# interlinkP2A.net
KiCad netlist of a schematic drawn in Altium Designer
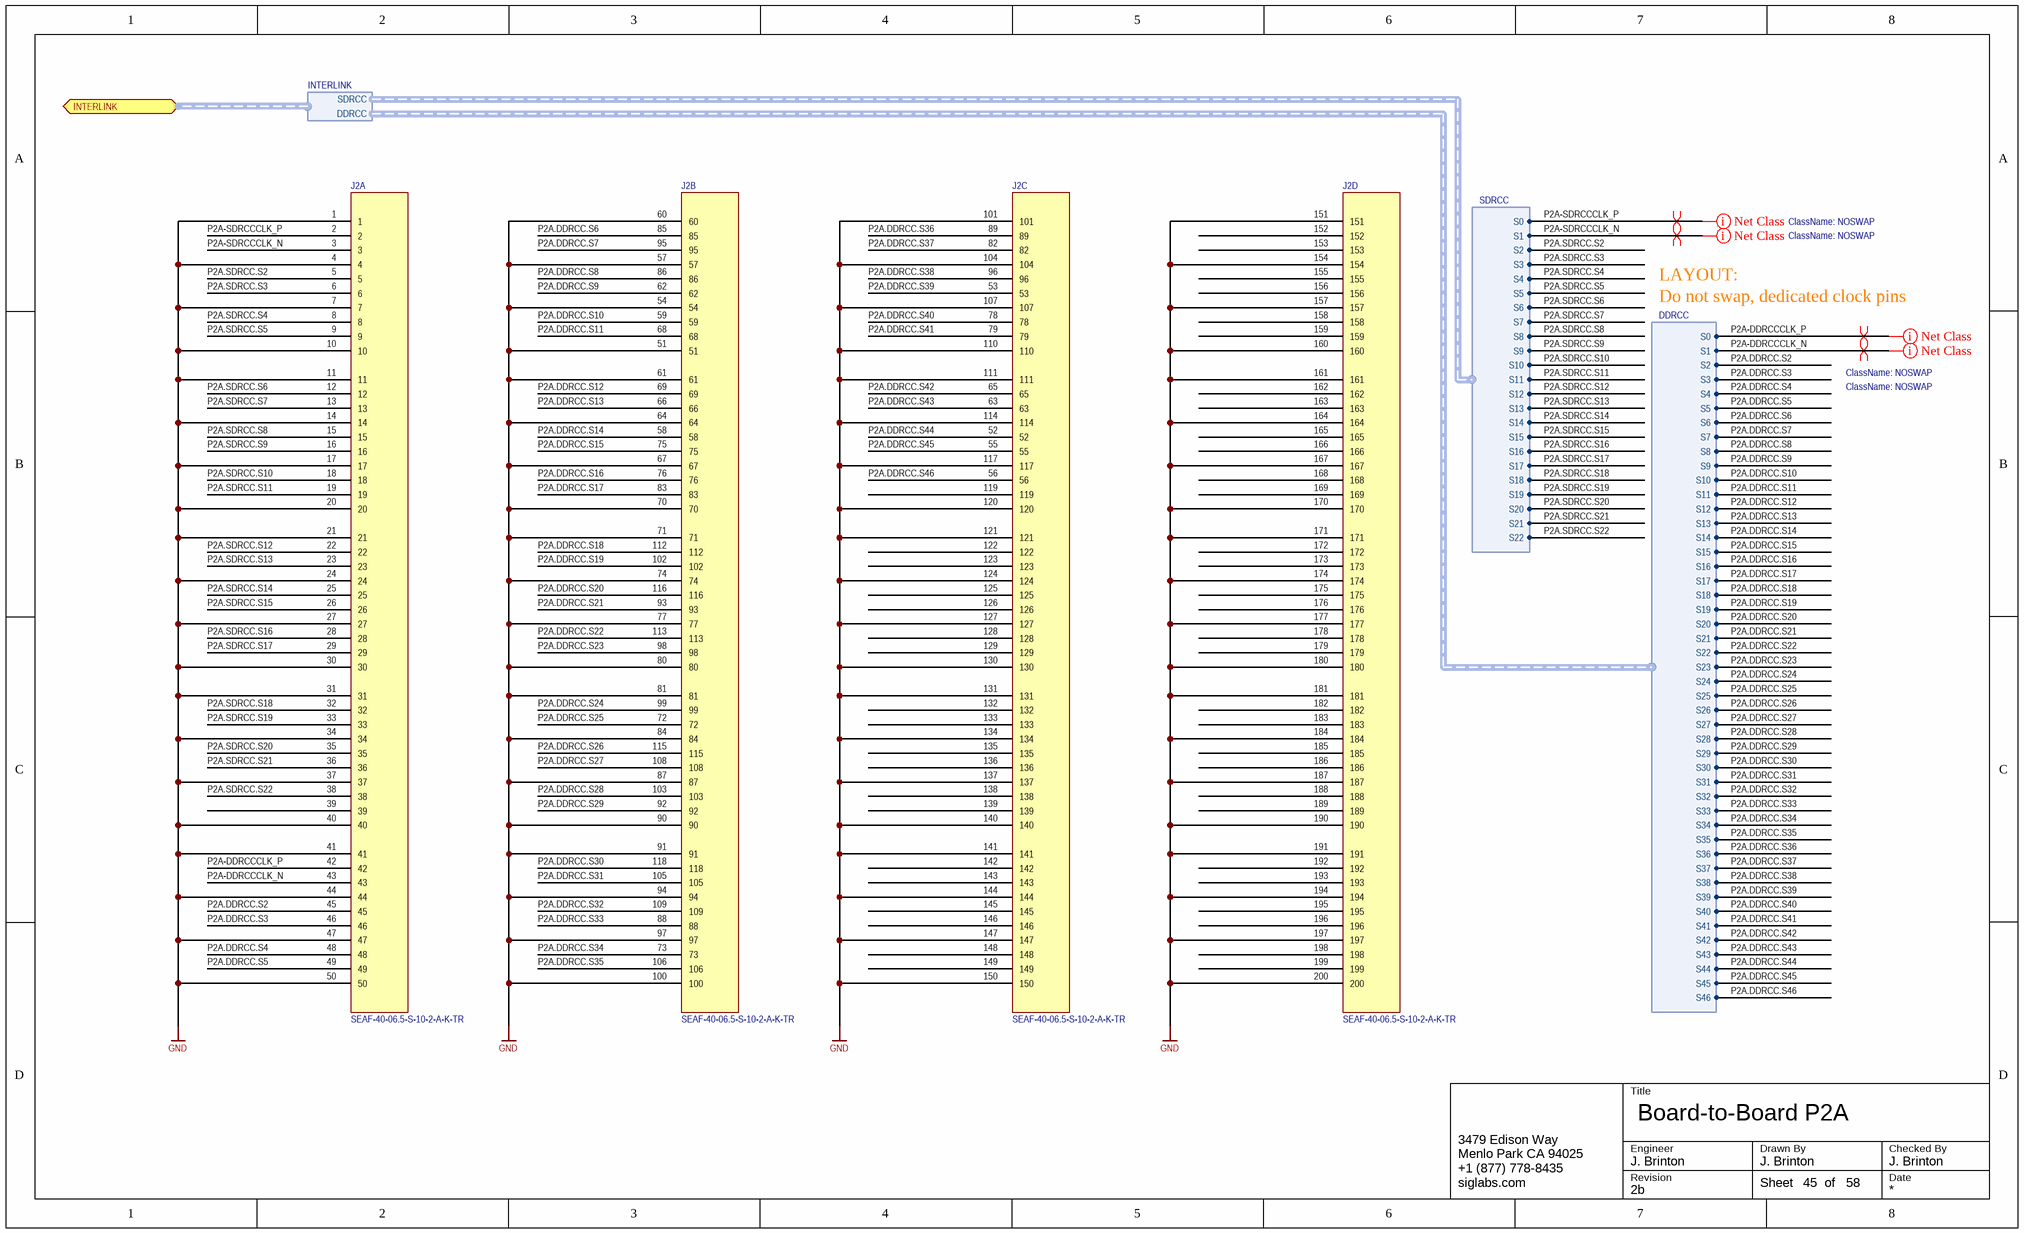
[diagram p0: interlinkP2A.SchDoc]

(export (version "E")
  (design (tool "Eeschema 10.0.6"))
  (components
    (comp (ref "J2")
      (value "SEAF-40-06.5-S-10-2-A-K-TR")
      (footprint "samtec:SEAF-40-06.5-S-10-2-A-K-TR")
      (description "Terminal Array Assembly, Surface Mount, 0.050\" Pitch, 400 Pins")
      (fields (field (name "MANUFACTURER") "Samtec"))
      (libsource (lib "samtec") (part "SEAF-40-06.5-S-10-2-A-K-TR"))
    )
  )
  (nets
    (net (code "5") (name "/P2A-DDRCCCLK_N") (class "Default")
      (node (ref "J2") (pin "43") (pinfunction "43_43") (pintype "passive"))
    )
    (net (code "6") (name "/P2A-DDRCCCLK_P") (class "Default")
      (node (ref "J2") (pin "42") (pinfunction "42_42") (pintype "passive"))
    )
    (net (code "7") (name "/P2A-SDRCCCLK_N") (class "Default")
      (node (ref "J2") (pin "3") (pinfunction "3_3") (pintype "passive"))
    )
    (net (code "8") (name "/P2A-SDRCCCLK_P") (class "Default")
      (node (ref "J2") (pin "2") (pinfunction "2_2") (pintype "passive"))
    )
    (net (code "9") (name "/P2A.DDRCC.S2") (class "Default")
      (node (ref "J2") (pin "45") (pinfunction "45_45") (pintype "passive"))
    )
    (net (code "10") (name "/P2A.DDRCC.S3") (class "Default")
      (node (ref "J2") (pin "46") (pinfunction "46_46") (pintype "passive"))
    )
    (net (code "11") (name "/P2A.DDRCC.S4") (class "Default")
      (node (ref "J2") (pin "48") (pinfunction "48_48") (pintype "passive"))
    )
    (net (code "12") (name "/P2A.DDRCC.S5") (class "Default")
      (node (ref "J2") (pin "49") (pinfunction "49_49") (pintype "passive"))
    )
    (net (code "13") (name "/P2A.DDRCC.S6") (class "Default")
      (node (ref "J2") (pin "85") (pinfunction "85_85") (pintype "passive"))
    )
    (net (code "14") (name "/P2A.DDRCC.S7") (class "Default")
      (node (ref "J2") (pin "95") (pinfunction "95_95") (pintype "passive"))
    )
    (net (code "15") (name "/P2A.DDRCC.S8") (class "Default")
      (node (ref "J2") (pin "86") (pinfunction "86_86") (pintype "passive"))
    )
    (net (code "16") (name "/P2A.DDRCC.S9") (class "Default")
      (node (ref "J2") (pin "62") (pinfunction "62_62") (pintype "passive"))
    )
    (net (code "17") (name "/P2A.DDRCC.S10") (class "Default")
      (node (ref "J2") (pin "59") (pinfunction "59_59") (pintype "passive"))
    )
    (net (code "18") (name "/P2A.DDRCC.S11") (class "Default")
      (node (ref "J2") (pin "68") (pinfunction "68_68") (pintype "passive"))
    )
    (net (code "19") (name "/P2A.DDRCC.S12") (class "Default")
      (node (ref "J2") (pin "69") (pinfunction "69_69") (pintype "passive"))
    )
    (net (code "20") (name "/P2A.DDRCC.S13") (class "Default")
      (node (ref "J2") (pin "66") (pinfunction "66_66") (pintype "passive"))
    )
    (net (code "21") (name "/P2A.DDRCC.S14") (class "Default")
      (node (ref "J2") (pin "58") (pinfunction "58_58") (pintype "passive"))
    )
    (net (code "22") (name "/P2A.DDRCC.S15") (class "Default")
      (node (ref "J2") (pin "75") (pinfunction "75_75") (pintype "passive"))
    )
    (net (code "23") (name "/P2A.DDRCC.S16") (class "Default")
      (node (ref "J2") (pin "76") (pinfunction "76_76") (pintype "passive"))
    )
    (net (code "24") (name "/P2A.DDRCC.S17") (class "Default")
      (node (ref "J2") (pin "83") (pinfunction "83_83") (pintype "passive"))
    )
    (net (code "25") (name "/P2A.DDRCC.S18") (class "Default")
      (node (ref "J2") (pin "112") (pinfunction "112_112") (pintype "passive"))
    )
    (net (code "26") (name "/P2A.DDRCC.S19") (class "Default")
      (node (ref "J2") (pin "102") (pinfunction "102_102") (pintype "passive"))
    )
    (net (code "27") (name "/P2A.DDRCC.S20") (class "Default")
      (node (ref "J2") (pin "116") (pinfunction "116_116") (pintype "passive"))
    )
    (net (code "28") (name "/P2A.DDRCC.S21") (class "Default")
      (node (ref "J2") (pin "93") (pinfunction "93_93") (pintype "passive"))
    )
    (net (code "29") (name "/P2A.DDRCC.S22") (class "Default")
      (node (ref "J2") (pin "113") (pinfunction "113_113") (pintype "passive"))
    )
    (net (code "30") (name "/P2A.DDRCC.S23") (class "Default")
      (node (ref "J2") (pin "98") (pinfunction "98_98") (pintype "passive"))
    )
    (net (code "31") (name "/P2A.DDRCC.S24") (class "Default")
      (node (ref "J2") (pin "99") (pinfunction "99_99") (pintype "passive"))
    )
    (net (code "32") (name "/P2A.DDRCC.S25") (class "Default")
      (node (ref "J2") (pin "72") (pinfunction "72_72") (pintype "passive"))
    )
    (net (code "33") (name "/P2A.DDRCC.S26") (class "Default")
      (node (ref "J2") (pin "115") (pinfunction "115_115") (pintype "passive"))
    )
    (net (code "34") (name "/P2A.DDRCC.S27") (class "Default")
      (node (ref "J2") (pin "108") (pinfunction "108_108") (pintype "passive"))
    )
    (net (code "35") (name "/P2A.DDRCC.S28") (class "Default")
      (node (ref "J2") (pin "103") (pinfunction "103_103") (pintype "passive"))
    )
    (net (code "36") (name "/P2A.DDRCC.S29") (class "Default")
      (node (ref "J2") (pin "92") (pinfunction "92_92") (pintype "passive"))
    )
    (net (code "37") (name "/P2A.DDRCC.S30") (class "Default")
      (node (ref "J2") (pin "118") (pinfunction "118_118") (pintype "passive"))
    )
    (net (code "38") (name "/P2A.DDRCC.S31") (class "Default")
      (node (ref "J2") (pin "105") (pinfunction "105_105") (pintype "passive"))
    )
    (net (code "39") (name "/P2A.DDRCC.S32") (class "Default")
      (node (ref "J2") (pin "109") (pinfunction "109_109") (pintype "passive"))
    )
    (net (code "40") (name "/P2A.DDRCC.S33") (class "Default")
      (node (ref "J2") (pin "88") (pinfunction "88_88") (pintype "passive"))
    )
    (net (code "41") (name "/P2A.DDRCC.S34") (class "Default")
      (node (ref "J2") (pin "73") (pinfunction "73_73") (pintype "passive"))
    )
    (net (code "42") (name "/P2A.DDRCC.S35") (class "Default")
      (node (ref "J2") (pin "106") (pinfunction "106_106") (pintype "passive"))
    )
    (net (code "43") (name "/P2A.DDRCC.S36") (class "Default")
      (node (ref "J2") (pin "89") (pinfunction "89_89") (pintype "passive"))
    )
    (net (code "44") (name "/P2A.DDRCC.S37") (class "Default")
      (node (ref "J2") (pin "82") (pinfunction "82_82") (pintype "passive"))
    )
    (net (code "45") (name "/P2A.DDRCC.S38") (class "Default")
      (node (ref "J2") (pin "96") (pinfunction "96_96") (pintype "passive"))
    )
    (net (code "46") (name "/P2A.DDRCC.S39") (class "Default")
      (node (ref "J2") (pin "53") (pinfunction "53_53") (pintype "passive"))
    )
    (net (code "47") (name "/P2A.DDRCC.S40") (class "Default")
      (node (ref "J2") (pin "78") (pinfunction "78_78") (pintype "passive"))
    )
    (net (code "48") (name "/P2A.DDRCC.S41") (class "Default")
      (node (ref "J2") (pin "79") (pinfunction "79_79") (pintype "passive"))
    )
    (net (code "49") (name "/P2A.DDRCC.S42") (class "Default")
      (node (ref "J2") (pin "65") (pinfunction "65_65") (pintype "passive"))
    )
    (net (code "50") (name "/P2A.DDRCC.S43") (class "Default")
      (node (ref "J2") (pin "63") (pinfunction "63_63") (pintype "passive"))
    )
    (net (code "51") (name "/P2A.DDRCC.S44") (class "Default")
      (node (ref "J2") (pin "52") (pinfunction "52_52") (pintype "passive"))
    )
    (net (code "52") (name "/P2A.DDRCC.S45") (class "Default")
      (node (ref "J2") (pin "55") (pinfunction "55_55") (pintype "passive"))
    )
    (net (code "53") (name "/P2A.DDRCC.S46") (class "Default")
      (node (ref "J2") (pin "56") (pinfunction "56_56") (pintype "passive"))
    )
    (net (code "54") (name "/P2A.SDRCC.S2") (class "Default")
      (node (ref "J2") (pin "5") (pinfunction "5_5") (pintype "passive"))
    )
    (net (code "55") (name "/P2A.SDRCC.S3") (class "Default")
      (node (ref "J2") (pin "6") (pinfunction "6_6") (pintype "passive"))
    )
    (net (code "56") (name "/P2A.SDRCC.S4") (class "Default")
      (node (ref "J2") (pin "8") (pinfunction "8_8") (pintype "passive"))
    )
    (net (code "57") (name "/P2A.SDRCC.S5") (class "Default")
      (node (ref "J2") (pin "9") (pinfunction "9_9") (pintype "passive"))
    )
    (net (code "58") (name "/P2A.SDRCC.S6") (class "Default")
      (node (ref "J2") (pin "12") (pinfunction "12_12") (pintype "passive"))
    )
    (net (code "59") (name "/P2A.SDRCC.S7") (class "Default")
      (node (ref "J2") (pin "13") (pinfunction "13_13") (pintype "passive"))
    )
    (net (code "60") (name "/P2A.SDRCC.S8") (class "Default")
      (node (ref "J2") (pin "15") (pinfunction "15_15") (pintype "passive"))
    )
    (net (code "61") (name "/P2A.SDRCC.S9") (class "Default")
      (node (ref "J2") (pin "16") (pinfunction "16_16") (pintype "passive"))
    )
    (net (code "62") (name "/P2A.SDRCC.S10") (class "Default")
      (node (ref "J2") (pin "18") (pinfunction "18_18") (pintype "passive"))
    )
    (net (code "63") (name "/P2A.SDRCC.S11") (class "Default")
      (node (ref "J2") (pin "19") (pinfunction "19_19") (pintype "passive"))
    )
    (net (code "64") (name "/P2A.SDRCC.S12") (class "Default")
      (node (ref "J2") (pin "22") (pinfunction "22_22") (pintype "passive"))
    )
    (net (code "65") (name "/P2A.SDRCC.S13") (class "Default")
      (node (ref "J2") (pin "23") (pinfunction "23_23") (pintype "passive"))
    )
    (net (code "66") (name "/P2A.SDRCC.S14") (class "Default")
      (node (ref "J2") (pin "25") (pinfunction "25_25") (pintype "passive"))
    )
    (net (code "67") (name "/P2A.SDRCC.S15") (class "Default")
      (node (ref "J2") (pin "26") (pinfunction "26_26") (pintype "passive"))
    )
    (net (code "68") (name "/P2A.SDRCC.S16") (class "Default")
      (node (ref "J2") (pin "28") (pinfunction "28_28") (pintype "passive"))
    )
    (net (code "69") (name "/P2A.SDRCC.S17") (class "Default")
      (node (ref "J2") (pin "29") (pinfunction "29_29") (pintype "passive"))
    )
    (net (code "70") (name "/P2A.SDRCC.S18") (class "Default")
      (node (ref "J2") (pin "32") (pinfunction "32_32") (pintype "passive"))
    )
    (net (code "71") (name "/P2A.SDRCC.S19") (class "Default")
      (node (ref "J2") (pin "33") (pinfunction "33_33") (pintype "passive"))
    )
    (net (code "72") (name "/P2A.SDRCC.S20") (class "Default")
      (node (ref "J2") (pin "35") (pinfunction "35_35") (pintype "passive"))
    )
    (net (code "73") (name "/P2A.SDRCC.S21") (class "Default")
      (node (ref "J2") (pin "36") (pinfunction "36_36") (pintype "passive"))
    )
    (net (code "74") (name "/P2A.SDRCC.S22") (class "Default")
      (node (ref "J2") (pin "38") (pinfunction "38_38") (pintype "passive"))
    )
    (net (code "77") (name "GND") (class "Default")
      (node (ref "J2") (pin "1") (pinfunction "1_1") (pintype "passive"))
      (node (ref "J2") (pin "10") (pinfunction "10_10") (pintype "passive"))
      (node (ref "J2") (pin "100") (pinfunction "100_100") (pintype "passive"))
      (node (ref "J2") (pin "101") (pinfunction "101_101") (pintype "passive"))
      (node (ref "J2") (pin "104") (pinfunction "104_104") (pintype "passive"))
      (node (ref "J2") (pin "107") (pinfunction "107_107") (pintype "passive"))
      (node (ref "J2") (pin "11") (pinfunction "11_11") (pintype "passive"))
      (node (ref "J2") (pin "110") (pinfunction "110_110") (pintype "passive"))
      (node (ref "J2") (pin "111") (pinfunction "111_111") (pintype "passive"))
      (node (ref "J2") (pin "114") (pinfunction "114_114") (pintype "passive"))
      (node (ref "J2") (pin "117") (pinfunction "117_117") (pintype "passive"))
      (node (ref "J2") (pin "120") (pinfunction "120_120") (pintype "passive"))
      (node (ref "J2") (pin "121") (pinfunction "121_121") (pintype "passive"))
      (node (ref "J2") (pin "124") (pinfunction "124_124") (pintype "passive"))
      (node (ref "J2") (pin "127") (pinfunction "127_127") (pintype "passive"))
      (node (ref "J2") (pin "130") (pinfunction "130_130") (pintype "passive"))
      (node (ref "J2") (pin "131") (pinfunction "131_131") (pintype "passive"))
      (node (ref "J2") (pin "134") (pinfunction "134_134") (pintype "passive"))
      (node (ref "J2") (pin "137") (pinfunction "137_137") (pintype "passive"))
      (node (ref "J2") (pin "14") (pinfunction "14_14") (pintype "passive"))
      (node (ref "J2") (pin "140") (pinfunction "140_140") (pintype "passive"))
      (node (ref "J2") (pin "141") (pinfunction "141_141") (pintype "passive"))
      (node (ref "J2") (pin "144") (pinfunction "144_144") (pintype "passive"))
      (node (ref "J2") (pin "147") (pinfunction "147_147") (pintype "passive"))
      (node (ref "J2") (pin "150") (pinfunction "150_150") (pintype "passive"))
      (node (ref "J2") (pin "151") (pinfunction "151_151") (pintype "passive"))
      (node (ref "J2") (pin "154") (pinfunction "154_154") (pintype "passive"))
      (node (ref "J2") (pin "157") (pinfunction "157_157") (pintype "passive"))
      (node (ref "J2") (pin "160") (pinfunction "160_160") (pintype "passive"))
      (node (ref "J2") (pin "161") (pinfunction "161_161") (pintype "passive"))
      (node (ref "J2") (pin "164") (pinfunction "164_164") (pintype "passive"))
      (node (ref "J2") (pin "167") (pinfunction "167_167") (pintype "passive"))
      (node (ref "J2") (pin "17") (pinfunction "17_17") (pintype "passive"))
      (node (ref "J2") (pin "170") (pinfunction "170_170") (pintype "passive"))
      (node (ref "J2") (pin "171") (pinfunction "171_171") (pintype "passive"))
      (node (ref "J2") (pin "174") (pinfunction "174_174") (pintype "passive"))
      (node (ref "J2") (pin "177") (pinfunction "177_177") (pintype "passive"))
      (node (ref "J2") (pin "180") (pinfunction "180_180") (pintype "passive"))
      (node (ref "J2") (pin "181") (pinfunction "181_181") (pintype "passive"))
      (node (ref "J2") (pin "184") (pinfunction "184_184") (pintype "passive"))
      (node (ref "J2") (pin "187") (pinfunction "187_187") (pintype "passive"))
      (node (ref "J2") (pin "190") (pinfunction "190_190") (pintype "passive"))
      (node (ref "J2") (pin "191") (pinfunction "191_191") (pintype "passive"))
      (node (ref "J2") (pin "194") (pinfunction "194_194") (pintype "passive"))
      (node (ref "J2") (pin "197") (pinfunction "197_197") (pintype "passive"))
      (node (ref "J2") (pin "20") (pinfunction "20_20") (pintype "passive"))
      (node (ref "J2") (pin "200") (pinfunction "200_200") (pintype "passive"))
      (node (ref "J2") (pin "21") (pinfunction "21_21") (pintype "passive"))
      (node (ref "J2") (pin "24") (pinfunction "24_24") (pintype "passive"))
      (node (ref "J2") (pin "27") (pinfunction "27_27") (pintype "passive"))
      (node (ref "J2") (pin "30") (pinfunction "30_30") (pintype "passive"))
      (node (ref "J2") (pin "31") (pinfunction "31_31") (pintype "passive"))
      (node (ref "J2") (pin "34") (pinfunction "34_34") (pintype "passive"))
      (node (ref "J2") (pin "37") (pinfunction "37_37") (pintype "passive"))
      (node (ref "J2") (pin "4") (pinfunction "4_4") (pintype "passive"))
      (node (ref "J2") (pin "40") (pinfunction "40_40") (pintype "passive"))
      (node (ref "J2") (pin "41") (pinfunction "41_41") (pintype "passive"))
      (node (ref "J2") (pin "44") (pinfunction "44_44") (pintype "passive"))
      (node (ref "J2") (pin "47") (pinfunction "47_47") (pintype "passive"))
      (node (ref "J2") (pin "50") (pinfunction "50_50") (pintype "passive"))
      (node (ref "J2") (pin "51") (pinfunction "51_51") (pintype "passive"))
      (node (ref "J2") (pin "54") (pinfunction "54_54") (pintype "passive"))
      (node (ref "J2") (pin "57") (pinfunction "57_57") (pintype "passive"))
      (node (ref "J2") (pin "60") (pinfunction "60_60") (pintype "passive"))
      (node (ref "J2") (pin "61") (pinfunction "61_61") (pintype "passive"))
      (node (ref "J2") (pin "64") (pinfunction "64_64") (pintype "passive"))
      (node (ref "J2") (pin "67") (pinfunction "67_67") (pintype "passive"))
      (node (ref "J2") (pin "7") (pinfunction "7_7") (pintype "passive"))
      (node (ref "J2") (pin "70") (pinfunction "70_70") (pintype "passive"))
      (node (ref "J2") (pin "71") (pinfunction "71_71") (pintype "passive"))
      (node (ref "J2") (pin "74") (pinfunction "74_74") (pintype "passive"))
      (node (ref "J2") (pin "77") (pinfunction "77_77") (pintype "passive"))
      (node (ref "J2") (pin "80") (pinfunction "80_80") (pintype "passive"))
      (node (ref "J2") (pin "81") (pinfunction "81_81") (pintype "passive"))
      (node (ref "J2") (pin "84") (pinfunction "84_84") (pintype "passive"))
      (node (ref "J2") (pin "87") (pinfunction "87_87") (pintype "passive"))
      (node (ref "J2") (pin "90") (pinfunction "90_90") (pintype "passive"))
      (node (ref "J2") (pin "91") (pinfunction "91_91") (pintype "passive"))
      (node (ref "J2") (pin "94") (pinfunction "94_94") (pintype "passive"))
      (node (ref "J2") (pin "97") (pinfunction "97_97") (pintype "passive"))
    )
    (net (code "78") (name "unconnected-(J2-Pad39)") (class "Default")
      (node (ref "J2") (pin "39") (pinfunction "39_39") (pintype "passive"))
    )
    (net (code "79") (name "unconnected-(J2-Pad119)") (class "Default")
      (node (ref "J2") (pin "119") (pinfunction "119_119") (pintype "passive"))
    )
    (net (code "80") (name "unconnected-(J2-Pad122)") (class "Default")
      (node (ref "J2") (pin "122") (pinfunction "122_122") (pintype "passive"))
    )
    (net (code "81") (name "unconnected-(J2-Pad123)") (class "Default")
      (node (ref "J2") (pin "123") (pinfunction "123_123") (pintype "passive"))
    )
    (net (code "82") (name "unconnected-(J2-Pad125)") (class "Default")
      (node (ref "J2") (pin "125") (pinfunction "125_125") (pintype "passive"))
    )
    (net (code "83") (name "unconnected-(J2-Pad126)") (class "Default")
      (node (ref "J2") (pin "126") (pinfunction "126_126") (pintype "passive"))
    )
    (net (code "84") (name "unconnected-(J2-Pad128)") (class "Default")
      (node (ref "J2") (pin "128") (pinfunction "128_128") (pintype "passive"))
    )
    (net (code "85") (name "unconnected-(J2-Pad129)") (class "Default")
      (node (ref "J2") (pin "129") (pinfunction "129_129") (pintype "passive"))
    )
    (net (code "86") (name "unconnected-(J2-Pad132)") (class "Default")
      (node (ref "J2") (pin "132") (pinfunction "132_132") (pintype "passive"))
    )
    (net (code "87") (name "unconnected-(J2-Pad133)") (class "Default")
      (node (ref "J2") (pin "133") (pinfunction "133_133") (pintype "passive"))
    )
    (net (code "88") (name "unconnected-(J2-Pad135)") (class "Default")
      (node (ref "J2") (pin "135") (pinfunction "135_135") (pintype "passive"))
    )
    (net (code "89") (name "unconnected-(J2-Pad136)") (class "Default")
      (node (ref "J2") (pin "136") (pinfunction "136_136") (pintype "passive"))
    )
    (net (code "90") (name "unconnected-(J2-Pad138)") (class "Default")
      (node (ref "J2") (pin "138") (pinfunction "138_138") (pintype "passive"))
    )
    (net (code "91") (name "unconnected-(J2-Pad139)") (class "Default")
      (node (ref "J2") (pin "139") (pinfunction "139_139") (pintype "passive"))
    )
    (net (code "92") (name "unconnected-(J2-Pad142)") (class "Default")
      (node (ref "J2") (pin "142") (pinfunction "142_142") (pintype "passive"))
    )
    (net (code "93") (name "unconnected-(J2-Pad143)") (class "Default")
      (node (ref "J2") (pin "143") (pinfunction "143_143") (pintype "passive"))
    )
    (net (code "94") (name "unconnected-(J2-Pad145)") (class "Default")
      (node (ref "J2") (pin "145") (pinfunction "145_145") (pintype "passive"))
    )
    (net (code "95") (name "unconnected-(J2-Pad146)") (class "Default")
      (node (ref "J2") (pin "146") (pinfunction "146_146") (pintype "passive"))
    )
    (net (code "96") (name "unconnected-(J2-Pad148)") (class "Default")
      (node (ref "J2") (pin "148") (pinfunction "148_148") (pintype "passive"))
    )
    (net (code "97") (name "unconnected-(J2-Pad149)") (class "Default")
      (node (ref "J2") (pin "149") (pinfunction "149_149") (pintype "passive"))
    )
    (net (code "98") (name "unconnected-(J2-Pad152)") (class "Default")
      (node (ref "J2") (pin "152") (pinfunction "152_152") (pintype "passive"))
    )
    (net (code "99") (name "unconnected-(J2-Pad153)") (class "Default")
      (node (ref "J2") (pin "153") (pinfunction "153_153") (pintype "passive"))
    )
    (net (code "100") (name "unconnected-(J2-Pad155)") (class "Default")
      (node (ref "J2") (pin "155") (pinfunction "155_155") (pintype "passive"))
    )
    (net (code "101") (name "unconnected-(J2-Pad156)") (class "Default")
      (node (ref "J2") (pin "156") (pinfunction "156_156") (pintype "passive"))
    )
    (net (code "102") (name "unconnected-(J2-Pad158)") (class "Default")
      (node (ref "J2") (pin "158") (pinfunction "158_158") (pintype "passive"))
    )
    (net (code "103") (name "unconnected-(J2-Pad159)") (class "Default")
      (node (ref "J2") (pin "159") (pinfunction "159_159") (pintype "passive"))
    )
    (net (code "104") (name "unconnected-(J2-Pad162)") (class "Default")
      (node (ref "J2") (pin "162") (pinfunction "162_162") (pintype "passive"))
    )
    (net (code "105") (name "unconnected-(J2-Pad163)") (class "Default")
      (node (ref "J2") (pin "163") (pinfunction "163_163") (pintype "passive"))
    )
    (net (code "106") (name "unconnected-(J2-Pad165)") (class "Default")
      (node (ref "J2") (pin "165") (pinfunction "165_165") (pintype "passive"))
    )
    (net (code "107") (name "unconnected-(J2-Pad166)") (class "Default")
      (node (ref "J2") (pin "166") (pinfunction "166_166") (pintype "passive"))
    )
    (net (code "108") (name "unconnected-(J2-Pad168)") (class "Default")
      (node (ref "J2") (pin "168") (pinfunction "168_168") (pintype "passive"))
    )
    (net (code "109") (name "unconnected-(J2-Pad169)") (class "Default")
      (node (ref "J2") (pin "169") (pinfunction "169_169") (pintype "passive"))
    )
    (net (code "110") (name "unconnected-(J2-Pad172)") (class "Default")
      (node (ref "J2") (pin "172") (pinfunction "172_172") (pintype "passive"))
    )
    (net (code "111") (name "unconnected-(J2-Pad173)") (class "Default")
      (node (ref "J2") (pin "173") (pinfunction "173_173") (pintype "passive"))
    )
    (net (code "112") (name "unconnected-(J2-Pad175)") (class "Default")
      (node (ref "J2") (pin "175") (pinfunction "175_175") (pintype "passive"))
    )
    (net (code "113") (name "unconnected-(J2-Pad176)") (class "Default")
      (node (ref "J2") (pin "176") (pinfunction "176_176") (pintype "passive"))
    )
    (net (code "114") (name "unconnected-(J2-Pad178)") (class "Default")
      (node (ref "J2") (pin "178") (pinfunction "178_178") (pintype "passive"))
    )
    (net (code "115") (name "unconnected-(J2-Pad179)") (class "Default")
      (node (ref "J2") (pin "179") (pinfunction "179_179") (pintype "passive"))
    )
    (net (code "116") (name "unconnected-(J2-Pad182)") (class "Default")
      (node (ref "J2") (pin "182") (pinfunction "182_182") (pintype "passive"))
    )
    (net (code "117") (name "unconnected-(J2-Pad183)") (class "Default")
      (node (ref "J2") (pin "183") (pinfunction "183_183") (pintype "passive"))
    )
    (net (code "118") (name "unconnected-(J2-Pad185)") (class "Default")
      (node (ref "J2") (pin "185") (pinfunction "185_185") (pintype "passive"))
    )
    (net (code "119") (name "unconnected-(J2-Pad186)") (class "Default")
      (node (ref "J2") (pin "186") (pinfunction "186_186") (pintype "passive"))
    )
    (net (code "120") (name "unconnected-(J2-Pad188)") (class "Default")
      (node (ref "J2") (pin "188") (pinfunction "188_188") (pintype "passive"))
    )
    (net (code "121") (name "unconnected-(J2-Pad189)") (class "Default")
      (node (ref "J2") (pin "189") (pinfunction "189_189") (pintype "passive"))
    )
    (net (code "122") (name "unconnected-(J2-Pad192)") (class "Default")
      (node (ref "J2") (pin "192") (pinfunction "192_192") (pintype "passive"))
    )
    (net (code "123") (name "unconnected-(J2-Pad193)") (class "Default")
      (node (ref "J2") (pin "193") (pinfunction "193_193") (pintype "passive"))
    )
    (net (code "124") (name "unconnected-(J2-Pad195)") (class "Default")
      (node (ref "J2") (pin "195") (pinfunction "195_195") (pintype "passive"))
    )
    (net (code "125") (name "unconnected-(J2-Pad196)") (class "Default")
      (node (ref "J2") (pin "196") (pinfunction "196_196") (pintype "passive"))
    )
    (net (code "126") (name "unconnected-(J2-Pad198)") (class "Default")
      (node (ref "J2") (pin "198") (pinfunction "198_198") (pintype "passive"))
    )
    (net (code "127") (name "unconnected-(J2-Pad199)") (class "Default")
      (node (ref "J2") (pin "199") (pinfunction "199_199") (pintype "passive"))
    )
  )
)
